# Sensore_di_allagamento.net
KiCad netlist of a schematic drawn in EAGLE
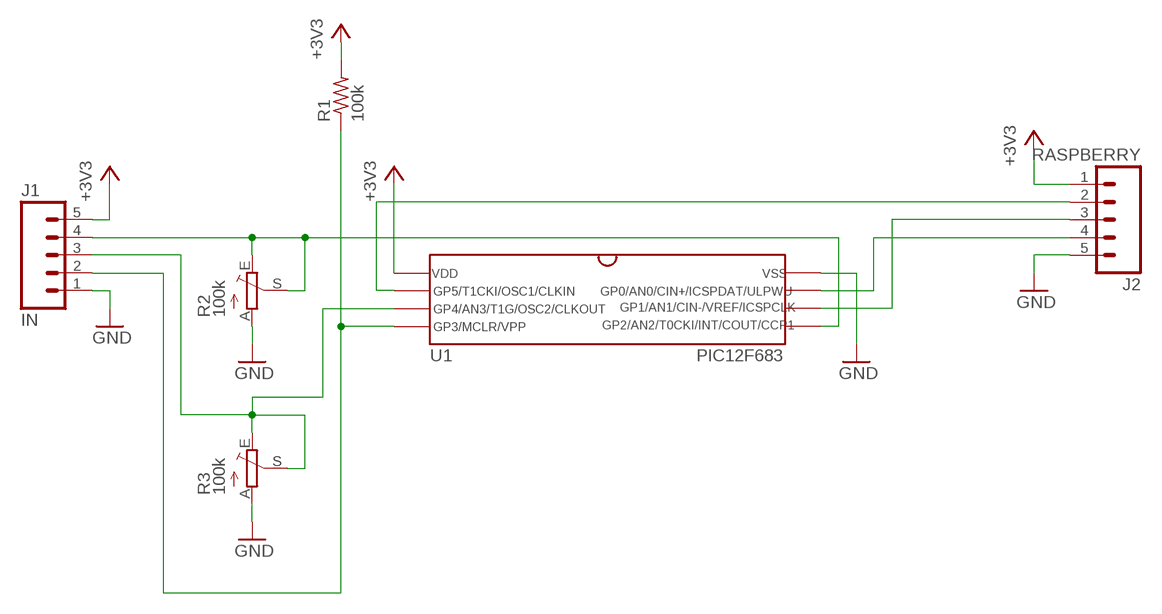
[diagram p0: schematic, sheet 1]

(export (version "E")
  (design (tool "Eeschema 10.0.6"))
  (components
    (comp (ref "J1")
      (value "IN")
      (footprint "eagle-import:JST-5-PTH-VERT")
      (libsource (lib "eagle-import") (part "M05JST-VERT"))
    )
    (comp (ref "J2")
      (value "RASPBERRY")
      (footprint "eagle-import:1X05")
      (libsource (lib "eagle-import") (part "M05PTH"))
    )
    (comp (ref "R1")
      (value "100k")
      (footprint "eagle-import:0207_15")
      (libsource (lib "eagle-import") (part "R-US_0207/15"))
    )
    (comp (ref "R2")
      (value "100k")
      (footprint "eagle-import:CA9V")
      (libsource (lib "eagle-import") (part "TRIM_EU-CA9V"))
    )
    (comp (ref "R3")
      (value "100k")
      (footprint "eagle-import:CA9V")
      (libsource (lib "eagle-import") (part "TRIM_EU-CA9V"))
    )
    (comp (ref "U1")
      (value "PIC12F683_RPDIP")
      (footprint "eagle-import:RPDIP-8PIN")
      (libsource (lib "eagle-import") (part "PIC12F683_RPDIP"))
    )
  )
  (nets
    (net (code "1") (name "+3V3") (class "Default")
      (node (ref "J1") (pin "5") (pinfunction "5_5") (pintype "passive"))
      (node (ref "J2") (pin "1") (pinfunction "1_1") (pintype "passive"))
      (node (ref "R1") (pin "2") (pinfunction "2_2") (pintype "passive"))
      (node (ref "U1") (pin "P$1") (pinfunction "P$1_P$1") (pintype "power_in"))
    )
    (net (code "2") (name "GND") (class "Default")
      (node (ref "J1") (pin "1") (pinfunction "1_1") (pintype "passive"))
      (node (ref "J2") (pin "5") (pinfunction "5_5") (pintype "passive"))
      (node (ref "R2") (pin "A") (pinfunction "A_A") (pintype "passive"))
      (node (ref "R3") (pin "A") (pinfunction "A_A") (pintype "passive"))
      (node (ref "U1") (pin "P$8") (pinfunction "P$8_P$8") (pintype "power_in"))
    )
    (net (code "3") (name "Net-(J1-Pad2)") (class "Default")
      (node (ref "J1") (pin "2") (pinfunction "2_2") (pintype "passive"))
      (node (ref "R1") (pin "1") (pinfunction "1_1") (pintype "passive"))
      (node (ref "U1") (pin "P$4") (pinfunction "P$4_P$4") (pintype "input"))
    )
    (net (code "4") (name "Net-(J1-Pad3)") (class "Default")
      (node (ref "J1") (pin "3") (pinfunction "3_3") (pintype "passive"))
      (node (ref "R3") (pin "E") (pinfunction "E_E") (pintype "passive"))
      (node (ref "R3") (pin "S") (pinfunction "S_S") (pintype "passive"))
      (node (ref "U1") (pin "P$3") (pinfunction "P$3_P$3") (pintype "bidirectional"))
    )
    (net (code "5") (name "Net-(J1-Pad4)") (class "Default")
      (node (ref "J1") (pin "4") (pinfunction "4_4") (pintype "passive"))
      (node (ref "R2") (pin "E") (pinfunction "E_E") (pintype "passive"))
      (node (ref "R2") (pin "S") (pinfunction "S_S") (pintype "passive"))
      (node (ref "U1") (pin "P$5") (pinfunction "P$5_P$5") (pintype "bidirectional"))
    )
    (net (code "6") (name "Net-(J2-Pad2)") (class "Default")
      (node (ref "J2") (pin "2") (pinfunction "2_2") (pintype "passive"))
      (node (ref "U1") (pin "P$2") (pinfunction "P$2_P$2") (pintype "bidirectional"))
    )
    (net (code "7") (name "Net-(J2-Pad3)") (class "Default")
      (node (ref "J2") (pin "3") (pinfunction "3_3") (pintype "passive"))
      (node (ref "U1") (pin "P$6") (pinfunction "P$6_P$6") (pintype "bidirectional"))
    )
    (net (code "8") (name "Net-(J2-Pad4)") (class "Default")
      (node (ref "J2") (pin "4") (pinfunction "4_4") (pintype "passive"))
      (node (ref "U1") (pin "P$7") (pinfunction "P$7_P$7") (pintype "bidirectional"))
    )
  )
)
